# 03_Template_MCU-sub_Power_Clock_Debug.net
KiCad netlist of a schematic drawn in Altium Designer
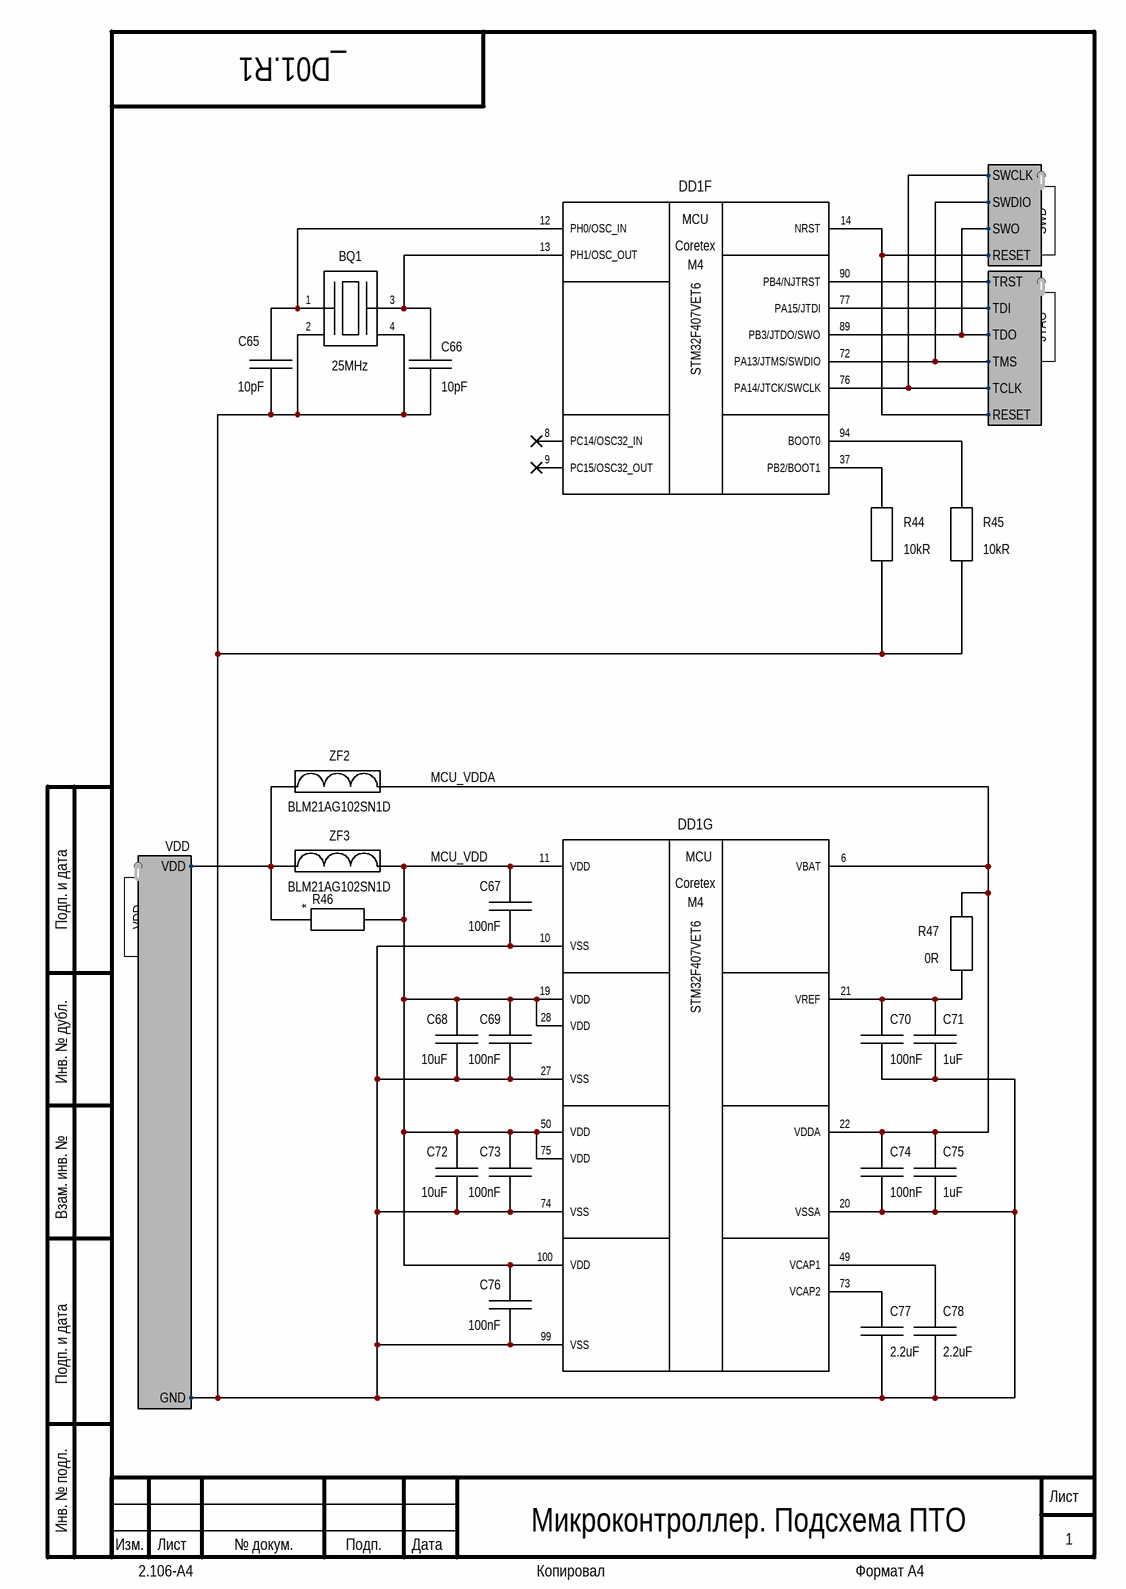
[diagram p0: 03.Template.MCU-sub.Power.Clock.Debug.SchDoc]

(export (version "E")
  (design (tool "Eeschema 10.0.6"))
  (components
    (comp (ref "BQ1")
      (value "25MHz")
      (footprint "CRYST3225-4N")
      (description "Crystal 25MHz 10pF")
      (fields (field (name "MANUFACTURER") "YXC"))
      (libsource (lib "Discrete_Oscillators_Cristal_SMD_GOST") (part "Oscillator_Cristal_B"))
    )
    (comp (ref "C65")
      (value "10pF")
      (footprint "CAPC2012N")
      (description "Capacitor Ceramic 10pF 50V C0G 2012")
      (fields (field (name "MANUFACTURER") "FH") (field (name "TOLERANCE") "±5%"))
      (libsource (lib "Discrete_Capacitors_Ceramic_2012_SMD_GOST") (part "Capacitor_A"))
    )
    (comp (ref "C66")
      (value "10pF")
      (footprint "CAPC2012N")
      (description "Capacitor Ceramic 10pF 50V C0G 2012")
      (fields (field (name "MANUFACTURER") "FH") (field (name "TOLERANCE") "±5%"))
      (libsource (lib "Discrete_Capacitors_Ceramic_2012_SMD_GOST") (part "Capacitor_A"))
    )
    (comp (ref "C67")
      (value "100nF")
      (footprint "CAPC2012N")
      (description "Capacitor Ceramic 100nF 50V X7R 2012")
      (fields (field (name "MANUFACTURER") "FH") (field (name "TOLERANCE") "±10%"))
      (libsource (lib "Discrete_Capacitors_Ceramic_2012_SMD_GOST") (part "Capacitor_A"))
    )
    (comp (ref "C68")
      (value "10uF")
      (footprint "CAPC2012N")
      (description "Capacitor Ceramic 10uF 50V X5R 2012")
      (fields (field (name "MANUFACTURER") "Murata Electronics") (field (name "TOLERANCE") "±10%"))
      (libsource (lib "Discrete_Capacitors_Ceramic_2012_SMD_GOST") (part "Capacitor_A"))
    )
    (comp (ref "C69")
      (value "100nF")
      (footprint "CAPC2012N")
      (description "Capacitor Ceramic 100nF 50V X7R 2012")
      (fields (field (name "MANUFACTURER") "FH") (field (name "TOLERANCE") "±10%"))
      (libsource (lib "Discrete_Capacitors_Ceramic_2012_SMD_GOST") (part "Capacitor_A"))
    )
    (comp (ref "C70")
      (value "100nF")
      (footprint "CAPC2012N")
      (description "Capacitor Ceramic 100nF 50V X7R 2012")
      (fields (field (name "MANUFACTURER") "FH") (field (name "TOLERANCE") "±10%"))
      (libsource (lib "Discrete_Capacitors_Ceramic_2012_SMD_GOST") (part "Capacitor_A"))
    )
    (comp (ref "C71")
      (value "1uF")
      (footprint "CAPC2012N")
      (description "Capacitor Ceramic 1uF 50V X7R 2012")
      (fields (field (name "MANUFACTURER") "FH") (field (name "TOLERANCE") "±10%"))
      (libsource (lib "Discrete_Capacitors_Ceramic_2012_SMD_GOST") (part "Capacitor_A"))
    )
    (comp (ref "C72")
      (value "10uF")
      (footprint "CAPC2012N")
      (description "Capacitor Ceramic 10uF 50V X5R 2012")
      (fields (field (name "MANUFACTURER") "Murata Electronics") (field (name "TOLERANCE") "±10%"))
      (libsource (lib "Discrete_Capacitors_Ceramic_2012_SMD_GOST") (part "Capacitor_A"))
    )
    (comp (ref "C73")
      (value "100nF")
      (footprint "CAPC2012N")
      (description "Capacitor Ceramic 100nF 50V X7R 2012")
      (fields (field (name "MANUFACTURER") "FH") (field (name "TOLERANCE") "±10%"))
      (libsource (lib "Discrete_Capacitors_Ceramic_2012_SMD_GOST") (part "Capacitor_A"))
    )
    (comp (ref "C74")
      (value "100nF")
      (footprint "CAPC2012N")
      (description "Capacitor Ceramic 100nF 50V X7R 2012")
      (fields (field (name "MANUFACTURER") "FH") (field (name "TOLERANCE") "±10%"))
      (libsource (lib "Discrete_Capacitors_Ceramic_2012_SMD_GOST") (part "Capacitor_A"))
    )
    (comp (ref "C75")
      (value "1uF")
      (footprint "CAPC2012N")
      (description "Capacitor Ceramic 1uF 50V X7R 2012")
      (fields (field (name "MANUFACTURER") "FH") (field (name "TOLERANCE") "±10%"))
      (libsource (lib "Discrete_Capacitors_Ceramic_2012_SMD_GOST") (part "Capacitor_A"))
    )
    (comp (ref "C76")
      (value "100nF")
      (footprint "CAPC2012N")
      (description "Capacitor Ceramic 100nF 50V X7R 2012")
      (fields (field (name "MANUFACTURER") "FH") (field (name "TOLERANCE") "±10%"))
      (libsource (lib "Discrete_Capacitors_Ceramic_2012_SMD_GOST") (part "Capacitor_A"))
    )
    (comp (ref "C77")
      (value "2.2uF")
      (footprint "CAPC2012N")
      (description "Capacitor Ceramic 2.2uF 50V X5R 2012")
      (fields (field (name "MANUFACTURER") "FH") (field (name "TOLERANCE") "±15%"))
      (libsource (lib "Discrete_Capacitors_Ceramic_2012_SMD_GOST") (part "Capacitor_A"))
    )
    (comp (ref "C78")
      (value "2.2uF")
      (footprint "CAPC2012N")
      (description "Capacitor Ceramic 2.2uF 50V X5R 2012")
      (fields (field (name "MANUFACTURER") "FH") (field (name "TOLERANCE") "±15%"))
      (libsource (lib "Discrete_Capacitors_Ceramic_2012_SMD_GOST") (part "Capacitor_A"))
    )
    (comp (ref "DD1")
      (value "STM32F407VET6")
      (footprint "LQFP-100N")
      (description "Microcontroller STM32F4 32b 168MHz 512kB Cortex-M4 LQFP-100")
      (fields (field (name "MANUFACTURER") "STMicroelectronics"))
      (libsource (lib "Digital_Microcontrollers_STM32_F4_SMD_GOST") (part "STM32F407Vx"))
    )
    (comp (ref "R44")
      (value "10kR")
      (footprint "RESC2012N")
      (description "Resistor Ceramic 10kR 1% 2012")
      (fields (field (name "MANUFACTURER") "UNI-ROYAL") (field (name "TOLERANCE") "±1%"))
      (libsource (lib "Discrete_Resistors_Ceramic_2012_1%_SMD_GOST") (part "Resistor_A"))
    )
    (comp (ref "R45")
      (value "10kR")
      (footprint "RESC2012N")
      (description "Resistor Ceramic 10kR 1% 2012")
      (fields (field (name "MANUFACTURER") "UNI-ROYAL") (field (name "TOLERANCE") "±1%"))
      (libsource (lib "Discrete_Resistors_Ceramic_2012_1%_SMD_GOST") (part "Resistor_A"))
    )
    (comp (ref "R46")
      (value "~")
      (footprint "RESC2012N-NM")
      (description "RESC NM 2012")
      (libsource (lib "Discrete_Resistors_Ceramic_General_SMD_GOST") (part "Resistor_A-NM"))
    )
    (comp (ref "R47")
      (value "0R")
      (footprint "RESC2012N")
      (description "Resistor Ceramic 0R 1% 2012")
      (fields (field (name "MANUFACTURER") "UNI-ROYAL") (field (name "TOLERANCE") "±1%"))
      (libsource (lib "Discrete_Resistors_Ceramic_2012_1%_SMD_GOST") (part "Resistor_A"))
    )
    (comp (ref "ZF2")
      (value "BLM21AG102SN1D")
      (footprint "FERB2012N")
      (description "Ferrite Bead 0.6A 1k/100MHz 2012")
      (fields (field (name "MANUFACTURER") "Murata Electronics"))
      (libsource (lib "Discrete_Filters_Beads_SMD_GOST") (part "Filter_Bead_A"))
    )
    (comp (ref "ZF3")
      (value "BLM21AG102SN1D")
      (footprint "FERB2012N")
      (description "Ferrite Bead 0.6A 1k/100MHz 2012")
      (fields (field (name "MANUFACTURER") "Murata Electronics"))
      (libsource (lib "Discrete_Filters_Beads_SMD_GOST") (part "Filter_Bead_A"))
    )
  )
  (nets
    (net (code "4") (name "/GND") (class "Default")
      (node (ref "BQ1") (pin "2") (pinfunction "2_2") (pintype "passive"))
      (node (ref "BQ1") (pin "4") (pinfunction "4_4") (pintype "passive"))
      (node (ref "C65") (pin "2") (pinfunction "2_2") (pintype "passive"))
      (node (ref "C66") (pin "2") (pinfunction "2_2") (pintype "passive"))
      (node (ref "C67") (pin "2") (pinfunction "2_2") (pintype "passive"))
      (node (ref "C68") (pin "2") (pinfunction "2_2") (pintype "passive"))
      (node (ref "C69") (pin "2") (pinfunction "2_2") (pintype "passive"))
      (node (ref "C70") (pin "2") (pinfunction "2_2") (pintype "passive"))
      (node (ref "C71") (pin "2") (pinfunction "2_2") (pintype "passive"))
      (node (ref "C72") (pin "2") (pinfunction "2_2") (pintype "passive"))
      (node (ref "C73") (pin "2") (pinfunction "2_2") (pintype "passive"))
      (node (ref "C74") (pin "2") (pinfunction "2_2") (pintype "passive"))
      (node (ref "C75") (pin "2") (pinfunction "2_2") (pintype "passive"))
      (node (ref "C76") (pin "2") (pinfunction "2_2") (pintype "passive"))
      (node (ref "C77") (pin "2") (pinfunction "2_2") (pintype "passive"))
      (node (ref "C78") (pin "2") (pinfunction "2_2") (pintype "passive"))
      (node (ref "DD1") (pin "10") (pinfunction "VSS_10") (pintype "passive"))
      (node (ref "DD1") (pin "20") (pinfunction "VSSA_20") (pintype "passive"))
      (node (ref "DD1") (pin "27") (pinfunction "VSS_27") (pintype "passive"))
      (node (ref "DD1") (pin "74") (pinfunction "VSS_74") (pintype "passive"))
      (node (ref "DD1") (pin "99") (pinfunction "VSS_99") (pintype "passive"))
      (node (ref "R44") (pin "2") (pinfunction "2_2") (pintype "passive"))
      (node (ref "R45") (pin "2") (pinfunction "2_2") (pintype "passive"))
    )
    (net (code "5") (name "/MCU_VDD") (class "Default")
      (node (ref "C67") (pin "1") (pinfunction "1_1") (pintype "passive"))
      (node (ref "C68") (pin "1") (pinfunction "1_1") (pintype "passive"))
      (node (ref "C69") (pin "1") (pinfunction "1_1") (pintype "passive"))
      (node (ref "C72") (pin "1") (pinfunction "1_1") (pintype "passive"))
      (node (ref "C73") (pin "1") (pinfunction "1_1") (pintype "passive"))
      (node (ref "C76") (pin "1") (pinfunction "1_1") (pintype "passive"))
      (node (ref "DD1") (pin "100") (pinfunction "VDD_100") (pintype "passive"))
      (node (ref "DD1") (pin "11") (pinfunction "VDD_11") (pintype "passive"))
      (node (ref "DD1") (pin "19") (pinfunction "VDD_19") (pintype "passive"))
      (node (ref "DD1") (pin "28") (pinfunction "VDD_28") (pintype "passive"))
      (node (ref "DD1") (pin "50") (pinfunction "VDD_50") (pintype "passive"))
      (node (ref "DD1") (pin "75") (pinfunction "VDD_75") (pintype "passive"))
      (node (ref "R46") (pin "2") (pinfunction "2_2") (pintype "passive"))
      (node (ref "ZF3") (pin "2") (pinfunction "2_2") (pintype "passive"))
    )
    (net (code "6") (name "/MCU_VDDA") (class "Default")
      (node (ref "C74") (pin "1") (pinfunction "1_1") (pintype "passive"))
      (node (ref "C75") (pin "1") (pinfunction "1_1") (pintype "passive"))
      (node (ref "DD1") (pin "22") (pinfunction "VDDA_22") (pintype "passive"))
      (node (ref "DD1") (pin "6") (pinfunction "VBAT_6") (pintype "passive"))
      (node (ref "R47") (pin "1") (pinfunction "1_1") (pintype "passive"))
      (node (ref "ZF2") (pin "2") (pinfunction "2_2") (pintype "passive"))
    )
    (net (code "7") (name "/RESET") (class "Default")
      (node (ref "DD1") (pin "14") (pinfunction "NRST_14") (pintype "passive"))
    )
    (net (code "8") (name "/SWCLK") (class "Default")
      (node (ref "DD1") (pin "76") (pinfunction "PA14/JTCK/SWCLK_76") (pintype "passive"))
    )
    (net (code "9") (name "/SWDIO") (class "Default")
      (node (ref "DD1") (pin "72") (pinfunction "PA13/JTMS/SWDIO_72") (pintype "passive"))
    )
    (net (code "11") (name "/SWO") (class "Default")
      (node (ref "DD1") (pin "89") (pinfunction "PB3/JTDO/SWO_89") (pintype "passive"))
    )
    (net (code "12") (name "/TDI") (class "Default")
      (node (ref "DD1") (pin "77") (pinfunction "PA15/JTDI_77") (pintype "passive"))
    )
    (net (code "13") (name "/TRST") (class "Default")
      (node (ref "DD1") (pin "90") (pinfunction "PB4/NJTRST_90") (pintype "passive"))
    )
    (net (code "16") (name "Net-(DD1F-BOOT0)") (class "Default")
      (node (ref "DD1") (pin "94") (pinfunction "BOOT0_94") (pintype "passive"))
      (node (ref "R45") (pin "1") (pinfunction "1_1") (pintype "passive"))
    )
    (net (code "17") (name "Net-(DD1F-PB2{slash}BOOT1)") (class "Default")
      (node (ref "DD1") (pin "37") (pinfunction "PB2/BOOT1_37") (pintype "passive"))
      (node (ref "R44") (pin "1") (pinfunction "1_1") (pintype "passive"))
    )
    (net (code "18") (name "Net-(DD1F-PH0{slash}OSC_IN)") (class "Default")
      (node (ref "BQ1") (pin "1") (pinfunction "1_1") (pintype "passive"))
      (node (ref "C65") (pin "1") (pinfunction "1_1") (pintype "passive"))
      (node (ref "DD1") (pin "12") (pinfunction "PH0/OSC_IN_12") (pintype "passive"))
    )
    (net (code "19") (name "Net-(DD1F-PH1{slash}OSC_OUT)") (class "Default")
      (node (ref "BQ1") (pin "3") (pinfunction "3_3") (pintype "passive"))
      (node (ref "C66") (pin "1") (pinfunction "1_1") (pintype "passive"))
      (node (ref "DD1") (pin "13") (pinfunction "PH1/OSC_OUT_13") (pintype "passive"))
    )
    (net (code "20") (name "Net-(DD1G-VCAP1)") (class "Default")
      (node (ref "C78") (pin "1") (pinfunction "1_1") (pintype "passive"))
      (node (ref "DD1") (pin "49") (pinfunction "VCAP1_49") (pintype "passive"))
    )
    (net (code "21") (name "Net-(DD1G-VCAP2)") (class "Default")
      (node (ref "C77") (pin "1") (pinfunction "1_1") (pintype "passive"))
      (node (ref "DD1") (pin "73") (pinfunction "VCAP2_73") (pintype "passive"))
    )
    (net (code "22") (name "Net-(DD1G-VREF)") (class "Default")
      (node (ref "C70") (pin "1") (pinfunction "1_1") (pintype "passive"))
      (node (ref "C71") (pin "1") (pinfunction "1_1") (pintype "passive"))
      (node (ref "DD1") (pin "21") (pinfunction "VREF_21") (pintype "passive"))
      (node (ref "R47") (pin "2") (pinfunction "2_2") (pintype "passive"))
    )
    (net (code "23") (name "Net-(R46-Pad1)") (class "Default")
      (node (ref "R46") (pin "1") (pinfunction "1_1") (pintype "passive"))
      (node (ref "ZF2") (pin "1") (pinfunction "1_1") (pintype "passive"))
      (node (ref "ZF3") (pin "1") (pinfunction "1_1") (pintype "passive"))
    )
    (net (code "24") (name "unconnected-(DD1F-PC14{slash}OSC32_IN-Pad8)") (class "Default")
      (node (ref "DD1") (pin "8") (pinfunction "PC14/OSC32_IN_8") (pintype "passive+no_connect"))
    )
    (net (code "25") (name "unconnected-(DD1F-PC15{slash}OSC32_OUT-Pad9)") (class "Default")
      (node (ref "DD1") (pin "9") (pinfunction "PC15/OSC32_OUT_9") (pintype "passive+no_connect"))
    )
  )
)
